# musicpulse.net
KiCad netlist of a schematic drawn in EAGLE
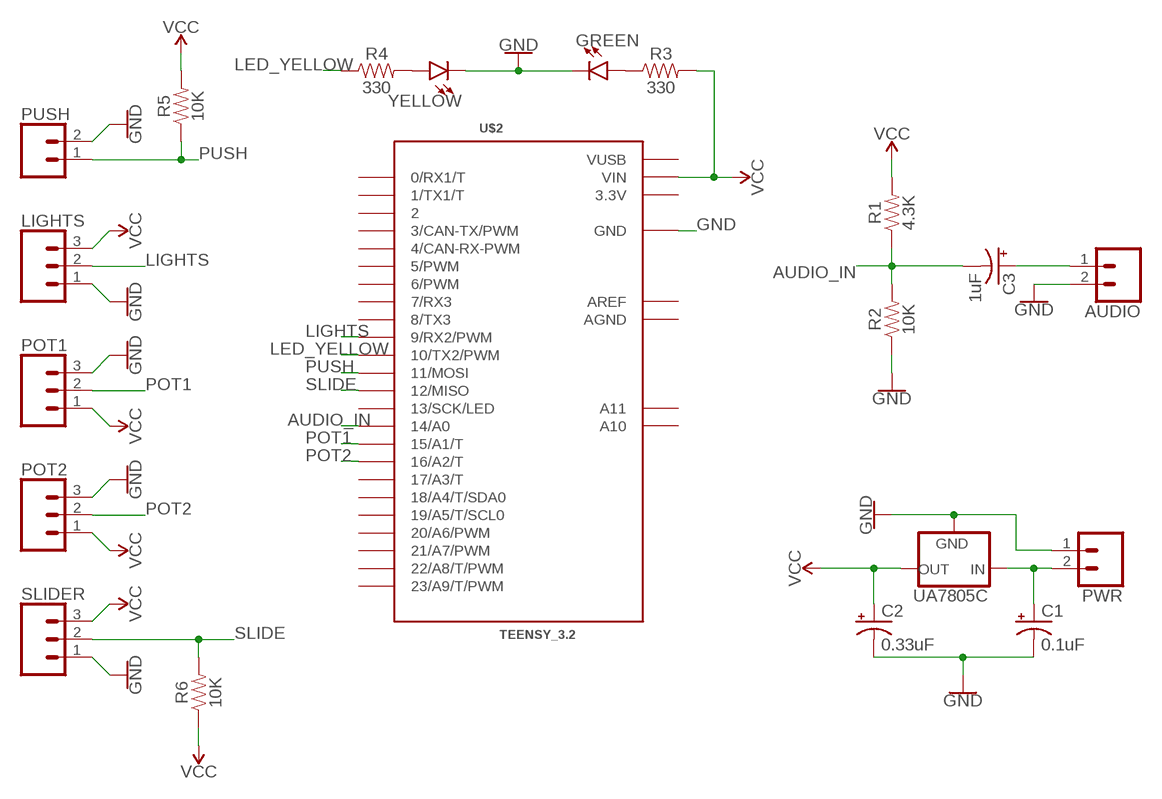
[diagram p0: schematic, sheet 1]

(export (version "E")
  (design (tool "Eeschema 10.0.6"))
  (components
    (comp (ref "AUDIO")
      (value "CONN_02")
      (footprint "eagle-import:1X02")
      (libsource (lib "eagle-import") (part "CONN_02"))
    )
    (comp (ref "C1")
      (value "0.1uF")
      (footprint "eagle-import:CPOL-RADIAL-2.5MM-5MM")
      (libsource (lib "eagle-import") (part "10UF-POLAR-RADIAL-2.5MM-25V-20%"))
    )
    (comp (ref "C2")
      (value "0.33uF")
      (footprint "eagle-import:CPOL-RADIAL-2.5MM-5MM")
      (libsource (lib "eagle-import") (part "10UF-POLAR-RADIAL-2.5MM-25V-20%"))
    )
    (comp (ref "C3")
      (value "1uF")
      (footprint "eagle-import:CPOL-RADIAL-2.5MM-5MM")
      (libsource (lib "eagle-import") (part "10UF-POLAR-RADIAL-2.5MM-25V-20%"))
    )
    (comp (ref "GREEN")
      (value "LED-3MM-NO_SILK")
      (footprint "eagle-import:LED_3MM-NS")
      (libsource (lib "eagle-import") (part "LED-3MM-NO_SILK"))
    )
    (comp (ref "LIGHTS")
      (value "CONN_03")
      (footprint "eagle-import:1X03")
      (libsource (lib "eagle-import") (part "CONN_03"))
    )
    (comp (ref "POT1")
      (value "CONN_03")
      (footprint "eagle-import:1X03")
      (libsource (lib "eagle-import") (part "CONN_03"))
    )
    (comp (ref "POT2")
      (value "CONN_03")
      (footprint "eagle-import:1X03")
      (libsource (lib "eagle-import") (part "CONN_03"))
    )
    (comp (ref "PUSH")
      (value "CONN_02")
      (footprint "eagle-import:1X02")
      (libsource (lib "eagle-import") (part "CONN_02"))
    )
    (comp (ref "PWR")
      (value "CONN_02")
      (footprint "eagle-import:1X02")
      (libsource (lib "eagle-import") (part "CONN_02"))
    )
    (comp (ref "R1")
      (value "4.3K")
      (footprint "eagle-import:AXIAL-0.3")
      (libsource (lib "eagle-import") (part "1KOHM-HORIZ-1/4W-1%"))
    )
    (comp (ref "R2")
      (value "10K")
      (footprint "eagle-import:AXIAL-0.3")
      (libsource (lib "eagle-import") (part "1KOHM-HORIZ-1/4W-1%"))
    )
    (comp (ref "R3")
      (value "330")
      (footprint "eagle-import:AXIAL-0.3")
      (libsource (lib "eagle-import") (part "1KOHM-HORIZ-1/4W-1%"))
    )
    (comp (ref "R4")
      (value "330")
      (footprint "eagle-import:AXIAL-0.3")
      (libsource (lib "eagle-import") (part "1KOHM-HORIZ-1/4W-1%"))
    )
    (comp (ref "R5")
      (value "10K")
      (footprint "eagle-import:AXIAL-0.3")
      (libsource (lib "eagle-import") (part "1KOHM-HORIZ-1/4W-1%"))
    )
    (comp (ref "R6")
      (value "10K")
      (footprint "eagle-import:AXIAL-0.3")
      (libsource (lib "eagle-import") (part "1KOHM-HORIZ-1/4W-1%"))
    )
    (comp (ref "SLIDER")
      (value "CONN_03")
      (footprint "eagle-import:1X03")
      (libsource (lib "eagle-import") (part "CONN_03"))
    )
    (comp (ref "U$2")
      (value "TEENSY_3.2")
      (footprint "eagle-import:TEENSY_3.0-3.2&LC_DIL+4")
      (libsource (lib "eagle-import") (part "TEENSY_3.1-3.2_DIL+4"))
    )
    (comp (ref "UA7805C")
      (value "V_REG_78XXSINK")
      (footprint "eagle-import:TO220-IGO")
      (libsource (lib "eagle-import") (part "V_REG_78XXSINK"))
    )
    (comp (ref "YELLOW")
      (value "LED-3MM-NO_SILK")
      (footprint "eagle-import:LED_3MM-NS")
      (libsource (lib "eagle-import") (part "LED-3MM-NO_SILK"))
    )
  )
  (nets
    (net (code "1") (name "/3.3V") (class "Default")
      (node (ref "U$2") (pin "3.3V") (pinfunction "3.3V_3.3V") (pintype "power_in"))
    )
    (net (code "2") (name "/AGND") (class "Default")
      (node (ref "U$2") (pin "AGND") (pinfunction "AGND_AGND") (pintype "power_in"))
    )
    (net (code "3") (name "/AREF") (class "Default")
      (node (ref "U$2") (pin "AREF") (pinfunction "AREF_AREF") (pintype "power_in"))
    )
    (net (code "4") (name "/AUDIO_IN") (class "Default")
      (node (ref "C3") (pin "2") (pinfunction "-_2") (pintype "passive"))
      (node (ref "R1") (pin "P$1") (pinfunction "1_P$1") (pintype "passive"))
      (node (ref "R2") (pin "P$2") (pinfunction "2_P$2") (pintype "passive"))
      (node (ref "U$2") (pin "14/A0") (pinfunction "14/A0_14/A0") (pintype "bidirectional"))
    )
    (net (code "5") (name "/LED_YELLOW") (class "Default")
      (node (ref "R4") (pin "P$1") (pinfunction "1_P$1") (pintype "passive"))
      (node (ref "U$2") (pin "10") (pinfunction "10/TX2/PWM_10") (pintype "bidirectional"))
    )
    (net (code "6") (name "/LIGHTS") (class "Default")
      (node (ref "LIGHTS") (pin "2") (pinfunction "2_2") (pintype "passive"))
      (node (ref "U$2") (pin "9") (pinfunction "9/RX2/PWM_9") (pintype "bidirectional"))
    )
    (net (code "7") (name "/POT1") (class "Default")
      (node (ref "POT1") (pin "2") (pinfunction "2_2") (pintype "passive"))
      (node (ref "U$2") (pin "15/A1") (pinfunction "15/A1/T_15/A1") (pintype "bidirectional"))
    )
    (net (code "8") (name "/POT2") (class "Default")
      (node (ref "POT2") (pin "2") (pinfunction "2_2") (pintype "passive"))
      (node (ref "U$2") (pin "16/A2") (pinfunction "16/A2/T_16/A2") (pintype "bidirectional"))
    )
    (net (code "9") (name "/PUSH") (class "Default")
      (node (ref "PUSH") (pin "1") (pinfunction "1_1") (pintype "passive"))
      (node (ref "R5") (pin "P$1") (pinfunction "1_P$1") (pintype "passive"))
      (node (ref "U$2") (pin "11") (pinfunction "11/MOSI_11") (pintype "bidirectional"))
    )
    (net (code "10") (name "/SLIDE") (class "Default")
      (node (ref "R6") (pin "P$2") (pinfunction "2_P$2") (pintype "passive"))
      (node (ref "SLIDER") (pin "2") (pinfunction "2_2") (pintype "passive"))
      (node (ref "U$2") (pin "12") (pinfunction "12/MISO_12") (pintype "bidirectional"))
    )
    (net (code "11") (name "/VUSB") (class "Default")
      (node (ref "U$2") (pin "VUSB") (pinfunction "VUSB_VUSB") (pintype "power_in"))
    )
    (net (code "12") (name "GND") (class "Default")
      (node (ref "AUDIO") (pin "2") (pinfunction "2_2") (pintype "passive"))
      (node (ref "C1") (pin "2") (pinfunction "-_2") (pintype "passive"))
      (node (ref "C2") (pin "2") (pinfunction "-_2") (pintype "passive"))
      (node (ref "GREEN") (pin "K") (pinfunction "C_K") (pintype "passive"))
      (node (ref "LIGHTS") (pin "1") (pinfunction "1_1") (pintype "passive"))
      (node (ref "POT1") (pin "3") (pinfunction "3_3") (pintype "passive"))
      (node (ref "POT2") (pin "3") (pinfunction "3_3") (pintype "passive"))
      (node (ref "PUSH") (pin "2") (pinfunction "2_2") (pintype "passive"))
      (node (ref "PWR") (pin "1") (pinfunction "1_1") (pintype "passive"))
      (node (ref "R2") (pin "P$1") (pinfunction "1_P$1") (pintype "passive"))
      (node (ref "SLIDER") (pin "1") (pinfunction "1_1") (pintype "passive"))
      (node (ref "U$2") (pin "GND") (pinfunction "GND_GND") (pintype "power_in"))
      (node (ref "UA7805C") (pin "GND") (pinfunction "GND_GND") (pintype "input"))
      (node (ref "YELLOW") (pin "K") (pinfunction "C_K") (pintype "passive"))
    )
    (net (code "13") (name "Net-(C1-+)") (class "Default")
      (node (ref "C1") (pin "1") (pinfunction "+_1") (pintype "passive"))
      (node (ref "PWR") (pin "2") (pinfunction "2_2") (pintype "passive"))
      (node (ref "UA7805C") (pin "IN") (pinfunction "IN_IN") (pintype "input"))
    )
    (net (code "14") (name "Net-(C3-+)") (class "Default")
      (node (ref "AUDIO") (pin "1") (pinfunction "1_1") (pintype "passive"))
      (node (ref "C3") (pin "1") (pinfunction "+_1") (pintype "passive"))
    )
    (net (code "15") (name "Net-(R3-1)") (class "Default")
      (node (ref "GREEN") (pin "A") (pinfunction "A_A") (pintype "passive"))
      (node (ref "R3") (pin "P$1") (pinfunction "1_P$1") (pintype "passive"))
    )
    (net (code "16") (name "Net-(R4-2)") (class "Default")
      (node (ref "R4") (pin "P$2") (pinfunction "2_P$2") (pintype "passive"))
      (node (ref "YELLOW") (pin "A") (pinfunction "A_A") (pintype "passive"))
    )
    (net (code "17") (name "VCC") (class "Default")
      (node (ref "C2") (pin "1") (pinfunction "+_1") (pintype "passive"))
      (node (ref "LIGHTS") (pin "3") (pinfunction "3_3") (pintype "passive"))
      (node (ref "POT1") (pin "1") (pinfunction "1_1") (pintype "passive"))
      (node (ref "POT2") (pin "1") (pinfunction "1_1") (pintype "passive"))
      (node (ref "R1") (pin "P$2") (pinfunction "2_P$2") (pintype "passive"))
      (node (ref "R3") (pin "P$2") (pinfunction "2_P$2") (pintype "passive"))
      (node (ref "R5") (pin "P$2") (pinfunction "2_P$2") (pintype "passive"))
      (node (ref "R6") (pin "P$1") (pinfunction "1_P$1") (pintype "passive"))
      (node (ref "SLIDER") (pin "3") (pinfunction "3_3") (pintype "passive"))
      (node (ref "U$2") (pin "VIN") (pinfunction "VIN_VIN") (pintype "power_in"))
      (node (ref "UA7805C") (pin "OUT") (pinfunction "OUT_OUT") (pintype "passive"))
    )
    (net (code "18") (name "unconnected-(U$2-0{slash}RX1{slash}T-Pad0)") (class "Default")
      (node (ref "U$2") (pin "0") (pinfunction "0/RX1/T_0") (pintype "bidirectional"))
    )
    (net (code "19") (name "unconnected-(U$2-1{slash}TX1{slash}T-Pad1)") (class "Default")
      (node (ref "U$2") (pin "1") (pinfunction "1/TX1/T_1") (pintype "bidirectional"))
    )
    (net (code "20") (name "unconnected-(U$2-3{slash}CAN-TX{slash}PWM-Pad3)") (class "Default")
      (node (ref "U$2") (pin "3") (pinfunction "3/CAN-TX/PWM_3") (pintype "bidirectional"))
    )
    (net (code "21") (name "unconnected-(U$2-4{slash}CAN-RX-PWM-Pad4)") (class "Default")
      (node (ref "U$2") (pin "4") (pinfunction "4/CAN-RX-PWM_4") (pintype "bidirectional"))
    )
    (net (code "22") (name "unconnected-(U$2-5{slash}PWM-Pad5)") (class "Default")
      (node (ref "U$2") (pin "5") (pinfunction "5/PWM_5") (pintype "bidirectional"))
    )
    (net (code "23") (name "unconnected-(U$2-6{slash}PWM-Pad6)") (class "Default")
      (node (ref "U$2") (pin "6") (pinfunction "6/PWM_6") (pintype "bidirectional"))
    )
    (net (code "24") (name "unconnected-(U$2-7{slash}RX3-Pad7)") (class "Default")
      (node (ref "U$2") (pin "7") (pinfunction "7/RX3_7") (pintype "bidirectional"))
    )
    (net (code "25") (name "unconnected-(U$2-8{slash}TX3-Pad8)") (class "Default")
      (node (ref "U$2") (pin "8") (pinfunction "8/TX3_8") (pintype "bidirectional"))
    )
    (net (code "26") (name "unconnected-(U$2-13{slash}SCK{slash}LED-Pad13)") (class "Default")
      (node (ref "U$2") (pin "13") (pinfunction "13/SCK/LED_13") (pintype "bidirectional"))
    )
    (net (code "27") (name "unconnected-(U$2-17{slash}A3{slash}T-Pad17{slash}A3)") (class "Default")
      (node (ref "U$2") (pin "17/A3") (pinfunction "17/A3/T_17/A3") (pintype "bidirectional"))
    )
    (net (code "28") (name "unconnected-(U$2-18{slash}A4{slash}T{slash}SDA0-Pad18{slash}A4)") (class "Default")
      (node (ref "U$2") (pin "18/A4") (pinfunction "18/A4/T/SDA0_18/A4") (pintype "bidirectional"))
    )
    (net (code "29") (name "unconnected-(U$2-19{slash}A5{slash}T{slash}SCL0-Pad19{slash}A5)") (class "Default")
      (node (ref "U$2") (pin "19/A5") (pinfunction "19/A5/T/SCL0_19/A5") (pintype "bidirectional"))
    )
    (net (code "30") (name "unconnected-(U$2-20{slash}A6{slash}PWM-Pad20{slash}A6)") (class "Default")
      (node (ref "U$2") (pin "20/A6") (pinfunction "20/A6/PWM_20/A6") (pintype "bidirectional"))
    )
    (net (code "31") (name "unconnected-(U$2-21{slash}A7{slash}PWM-Pad21{slash}A7)") (class "Default")
      (node (ref "U$2") (pin "21/A7") (pinfunction "21/A7/PWM_21/A7") (pintype "bidirectional"))
    )
    (net (code "32") (name "unconnected-(U$2-22{slash}A8{slash}T{slash}PWM-Pad22{slash}A8)") (class "Default")
      (node (ref "U$2") (pin "22/A8") (pinfunction "22/A8/T/PWM_22/A8") (pintype "bidirectional"))
    )
    (net (code "33") (name "unconnected-(U$2-23{slash}A9{slash}T{slash}PWM-Pad23{slash}A9)") (class "Default")
      (node (ref "U$2") (pin "23/A9") (pinfunction "23/A9/T/PWM_23/A9") (pintype "bidirectional"))
    )
    (net (code "34") (name "unconnected-(U$2-Pad2)") (class "Default")
      (node (ref "U$2") (pin "2") (pinfunction "2_2") (pintype "bidirectional"))
    )
    (net (code "35") (name "unconnected-(U$2-PadA10)") (class "Default")
      (node (ref "U$2") (pin "A10") (pinfunction "A10_A10") (pintype "bidirectional"))
    )
    (net (code "36") (name "unconnected-(U$2-PadA11)") (class "Default")
      (node (ref "U$2") (pin "A11") (pinfunction "A11_A11") (pintype "bidirectional"))
    )
  )
)
